# VCADual_Test.net
KiCad netlist of a schematic drawn in EAGLE
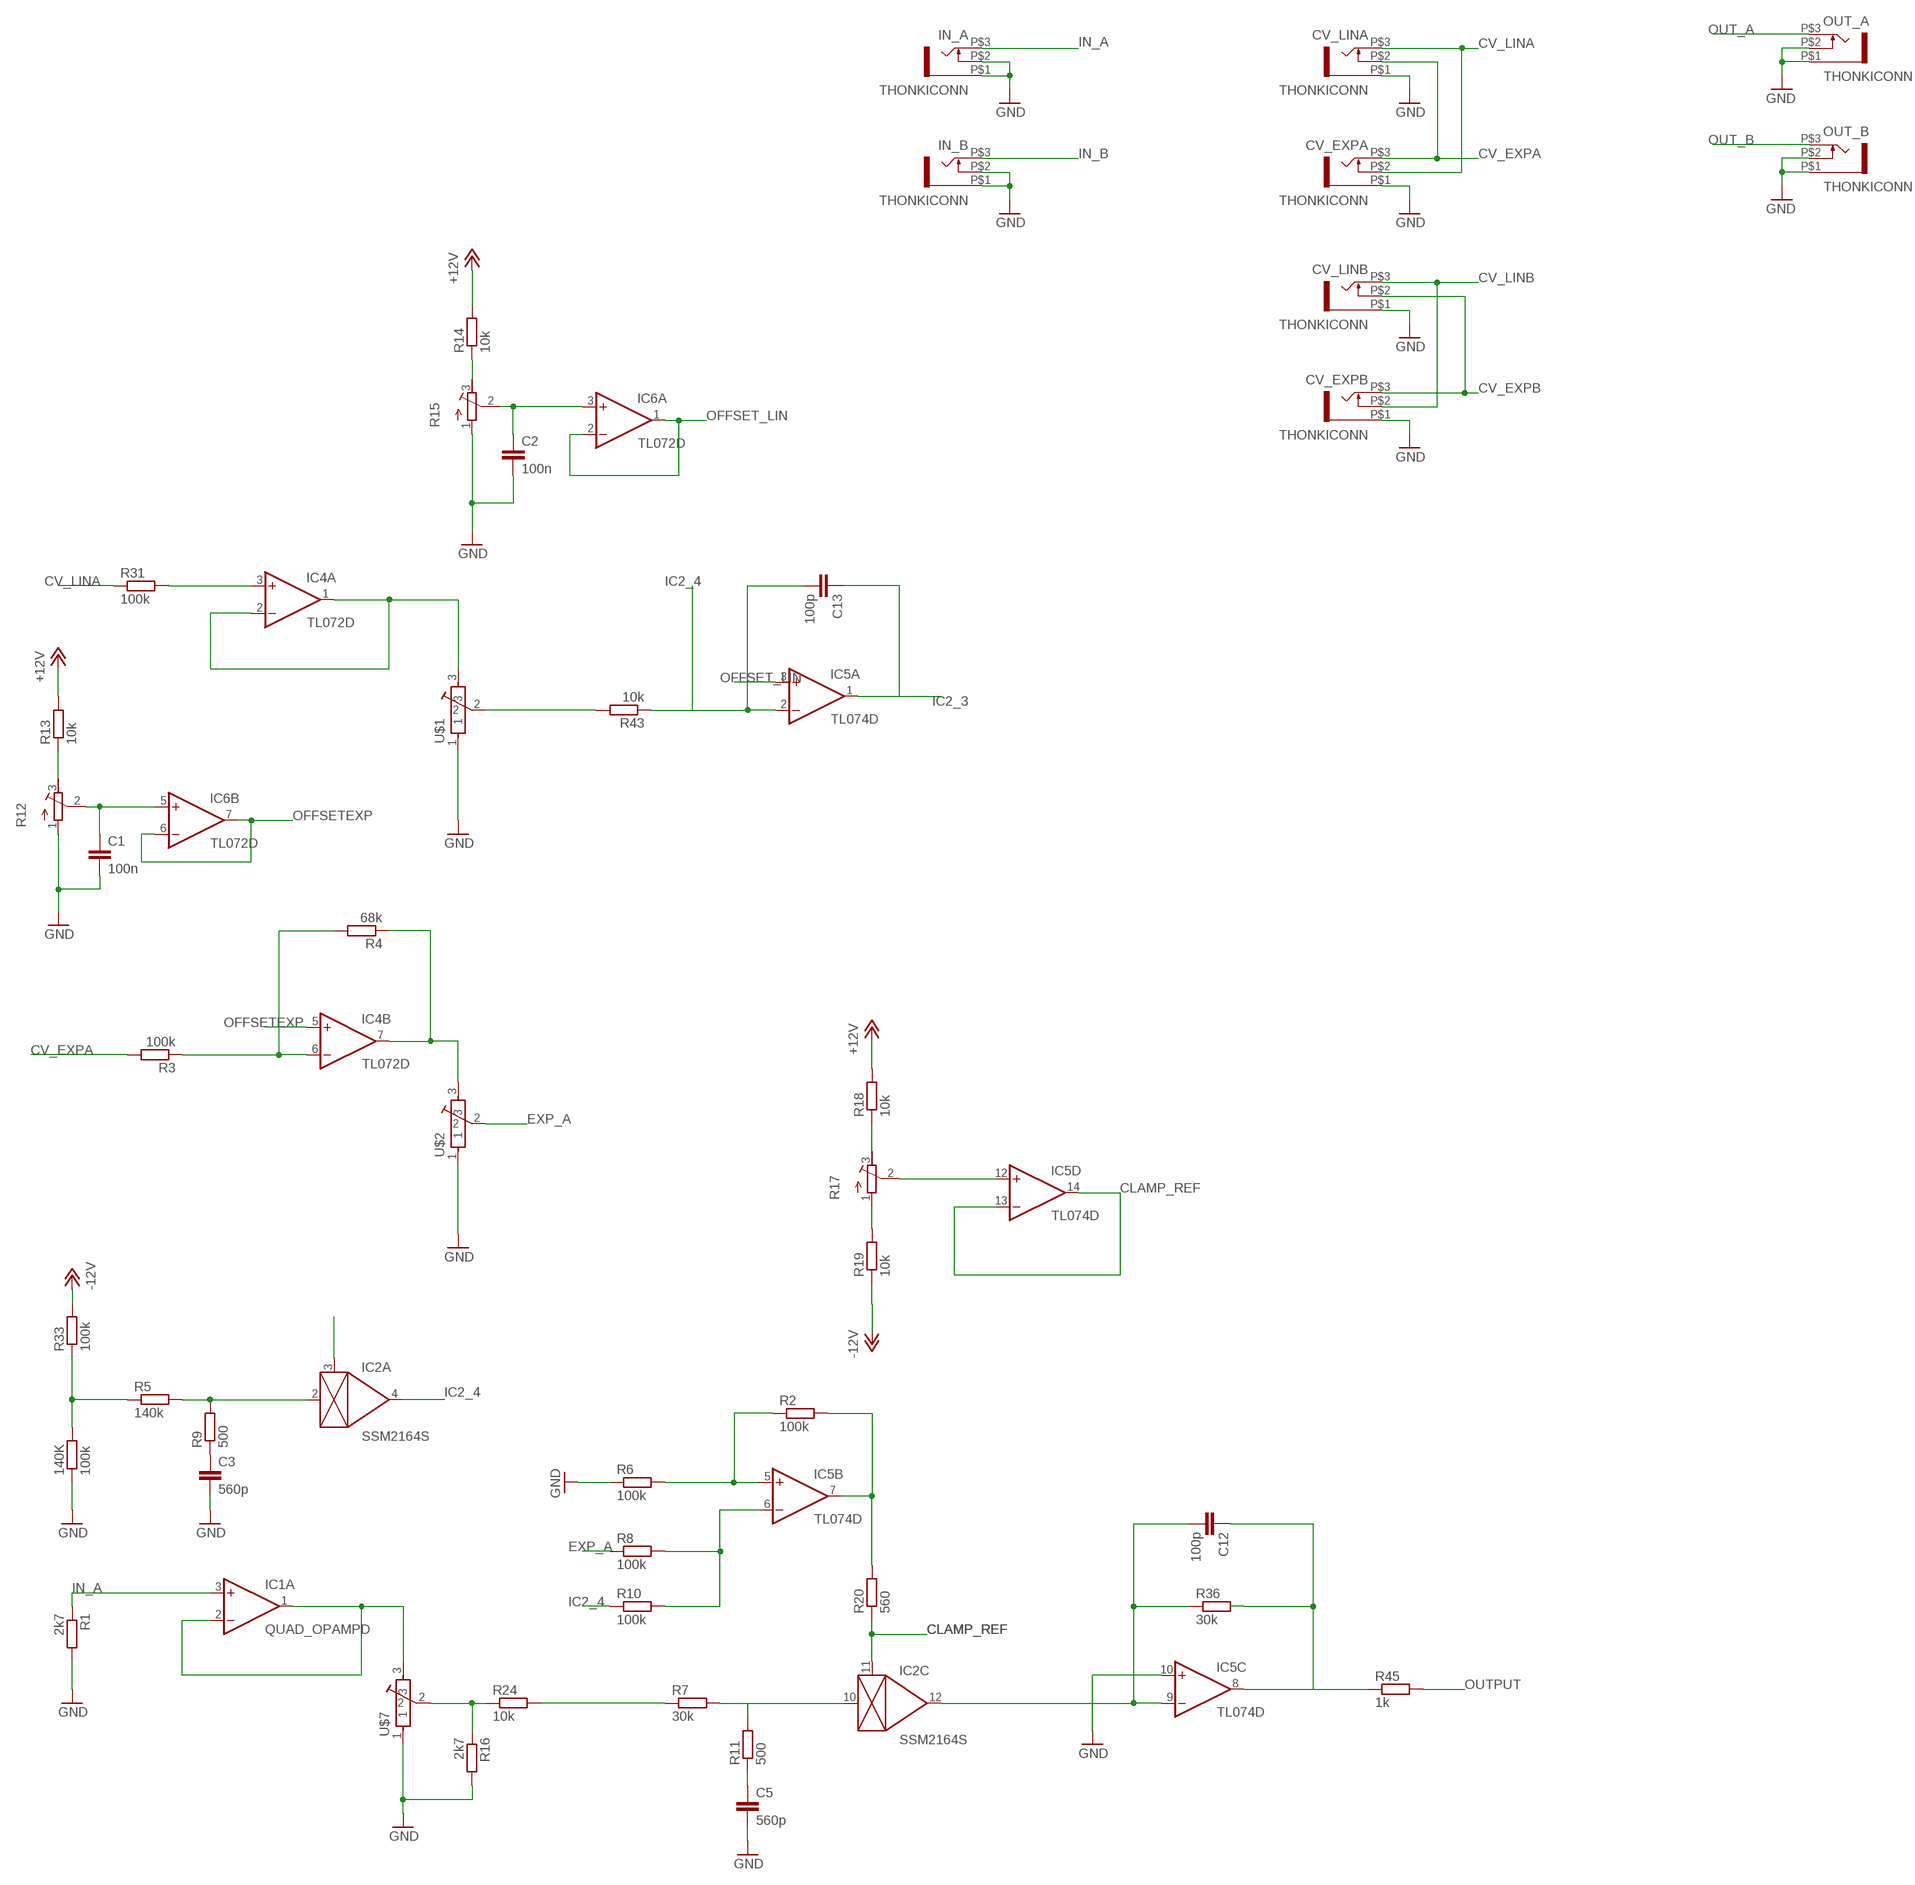
[diagram p0: schematic, sheet 1]

(export (version "E")
  (design (tool "Eeschema 10.0.6"))
  (components
    (comp (ref "140K")
      (value "100k")
      (footprint "eagle-import:0603")
      (libsource (lib "eagle-import") (part "R-EU_0603"))
    )
    (comp (ref "C1")
      (value "100n")
      (footprint "eagle-import:C0603K")
      (libsource (lib "eagle-import") (part "C-EUC0603K"))
    )
    (comp (ref "C2")
      (value "100n")
      (footprint "eagle-import:C0603K")
      (libsource (lib "eagle-import") (part "C-EUC0603K"))
    )
    (comp (ref "C3")
      (value "560p")
      (footprint "eagle-import:C0603K")
      (libsource (lib "eagle-import") (part "C-EUC0603K"))
    )
    (comp (ref "C5")
      (value "560p")
      (footprint "eagle-import:C0603K")
      (libsource (lib "eagle-import") (part "C-EUC0603K"))
    )
    (comp (ref "C12")
      (value "100p")
      (footprint "eagle-import:C0603K")
      (libsource (lib "eagle-import") (part "C-EUC0603K"))
    )
    (comp (ref "C13")
      (value "100p")
      (footprint "eagle-import:C0603K")
      (libsource (lib "eagle-import") (part "C-EUC0603K"))
    )
    (comp (ref "CV_EXPA")
      (value "THONKICONN")
      (footprint "eagle-import:THONKICONN")
      (libsource (lib "eagle-import") (part "THONKICONN"))
    )
    (comp (ref "CV_EXPB")
      (value "THONKICONN")
      (footprint "eagle-import:THONKICONN")
      (libsource (lib "eagle-import") (part "THONKICONN"))
    )
    (comp (ref "CV_LINA")
      (value "THONKICONN")
      (footprint "eagle-import:THONKICONN")
      (libsource (lib "eagle-import") (part "THONKICONN"))
    )
    (comp (ref "CV_LINB")
      (value "THONKICONN")
      (footprint "eagle-import:THONKICONN")
      (libsource (lib "eagle-import") (part "THONKICONN"))
    )
    (comp (ref "IC1")
      (value "QUAD_OPAMPD")
      (footprint "eagle-import:SO14")
      (libsource (lib "eagle-import") (part "QUAD_OPAMPD"))
    )
    (comp (ref "IC2")
      (value "SSM2164S")
      (footprint "eagle-import:SOIC16N")
      (libsource (lib "eagle-import") (part "SSM2164S"))
    )
    (comp (ref "IC4")
      (value "TL072D")
      (footprint "eagle-import:SO08")
      (libsource (lib "eagle-import") (part "TL072D"))
    )
    (comp (ref "IC5")
      (value "TL074D")
      (footprint "eagle-import:SO14")
      (libsource (lib "eagle-import") (part "TL074D"))
    )
    (comp (ref "IC6")
      (value "TL072D")
      (footprint "eagle-import:SO08")
      (libsource (lib "eagle-import") (part "TL072D"))
    )
    (comp (ref "IN_A")
      (value "THONKICONN")
      (footprint "eagle-import:THONKICONN")
      (libsource (lib "eagle-import") (part "THONKICONN"))
    )
    (comp (ref "IN_B")
      (value "THONKICONN")
      (footprint "eagle-import:THONKICONN")
      (libsource (lib "eagle-import") (part "THONKICONN"))
    )
    (comp (ref "OUT_A")
      (value "THONKICONN")
      (footprint "eagle-import:THONKICONN")
      (libsource (lib "eagle-import") (part "THONKICONN"))
    )
    (comp (ref "OUT_B")
      (value "THONKICONN")
      (footprint "eagle-import:THONKICONN")
      (libsource (lib "eagle-import") (part "THONKICONN"))
    )
    (comp (ref "R1")
      (value "2k7")
      (footprint "eagle-import:0603")
      (libsource (lib "eagle-import") (part "R-EU_0603"))
    )
    (comp (ref "R2")
      (value "100k")
      (footprint "eagle-import:0603")
      (libsource (lib "eagle-import") (part "R-EU_0603"))
    )
    (comp (ref "R3")
      (value "100k")
      (footprint "eagle-import:0603")
      (libsource (lib "eagle-import") (part "R-EU_0603"))
    )
    (comp (ref "R4")
      (value "68k")
      (footprint "eagle-import:0603")
      (libsource (lib "eagle-import") (part "R-EU_0603"))
    )
    (comp (ref "R5")
      (value "140k")
      (footprint "eagle-import:0603")
      (libsource (lib "eagle-import") (part "R-EU_0603"))
    )
    (comp (ref "R6")
      (value "100k")
      (footprint "eagle-import:0603")
      (libsource (lib "eagle-import") (part "R-EU_0603"))
    )
    (comp (ref "R7")
      (value "30k")
      (footprint "eagle-import:0603")
      (libsource (lib "eagle-import") (part "R-EU_0603"))
    )
    (comp (ref "R8")
      (value "100k")
      (footprint "eagle-import:0603")
      (libsource (lib "eagle-import") (part "R-EU_0603"))
    )
    (comp (ref "R9")
      (value "500")
      (footprint "eagle-import:0603")
      (libsource (lib "eagle-import") (part "R-EU_0603"))
    )
    (comp (ref "R10")
      (value "100k")
      (footprint "eagle-import:0603")
      (libsource (lib "eagle-import") (part "R-EU_0603"))
    )
    (comp (ref "R11")
      (value "500")
      (footprint "eagle-import:0603")
      (libsource (lib "eagle-import") (part "R-EU_0603"))
    )
    (comp (ref "R12")
      (value "R-TRIMM64X")
      (footprint "eagle-import:RTRIM64X")
      (libsource (lib "eagle-import") (part "R-TRIMM64X"))
    )
    (comp (ref "R13")
      (value "10k")
      (footprint "eagle-import:0603")
      (libsource (lib "eagle-import") (part "R-EU_0603"))
    )
    (comp (ref "R14")
      (value "10k")
      (footprint "eagle-import:0603")
      (libsource (lib "eagle-import") (part "R-EU_0603"))
    )
    (comp (ref "R15")
      (value "R-TRIMM64X")
      (footprint "eagle-import:RTRIM64X")
      (libsource (lib "eagle-import") (part "R-TRIMM64X"))
    )
    (comp (ref "R16")
      (value "2k7")
      (footprint "eagle-import:0603")
      (libsource (lib "eagle-import") (part "R-EU_0603"))
    )
    (comp (ref "R17")
      (value "R-TRIMM64X")
      (footprint "eagle-import:RTRIM64X")
      (libsource (lib "eagle-import") (part "R-TRIMM64X"))
    )
    (comp (ref "R18")
      (value "10k")
      (footprint "eagle-import:0603")
      (libsource (lib "eagle-import") (part "R-EU_0603"))
    )
    (comp (ref "R19")
      (value "10k")
      (footprint "eagle-import:0603")
      (libsource (lib "eagle-import") (part "R-EU_0603"))
    )
    (comp (ref "R20")
      (value "560")
      (footprint "eagle-import:0603")
      (libsource (lib "eagle-import") (part "R-EU_0603"))
    )
    (comp (ref "R24")
      (value "10k")
      (footprint "eagle-import:0603")
      (libsource (lib "eagle-import") (part "R-EU_0603"))
    )
    (comp (ref "R31")
      (value "100k")
      (footprint "eagle-import:0603")
      (libsource (lib "eagle-import") (part "R-EU_0603"))
    )
    (comp (ref "R33")
      (value "100k")
      (footprint "eagle-import:0603")
      (libsource (lib "eagle-import") (part "R-EU_0603"))
    )
    (comp (ref "R36")
      (value "30k")
      (footprint "eagle-import:0603")
      (libsource (lib "eagle-import") (part "R-EU_0603"))
    )
    (comp (ref "R43")
      (value "10k")
      (footprint "eagle-import:0603")
      (libsource (lib "eagle-import") (part "R-EU_0603"))
    )
    (comp (ref "R45")
      (value "1k")
      (footprint "eagle-import:0603")
      (libsource (lib "eagle-import") (part "R-EU_0603"))
    )
    (comp (ref "U$1")
      (value "POT-ALPS-RK09L1140")
      (footprint "eagle-import:POT-ALPS-RK09L1140")
      (libsource (lib "eagle-import") (part "POT-ALPS-RK09L1140"))
    )
    (comp (ref "U$2")
      (value "POT-ALPS-RK09L1140")
      (footprint "eagle-import:POT-ALPS-RK09L1140")
      (libsource (lib "eagle-import") (part "POT-ALPS-RK09L1140"))
    )
    (comp (ref "U$7")
      (value "POT-ALPS-RK09L1140")
      (footprint "eagle-import:POT-ALPS-RK09L1140")
      (libsource (lib "eagle-import") (part "POT-ALPS-RK09L1140"))
    )
  )
  (nets
    (net (code "1") (name "+12V") (class "Default")
      (node (ref "R13") (pin "2") (pinfunction "2_2") (pintype "passive"))
      (node (ref "R14") (pin "2") (pinfunction "2_2") (pintype "passive"))
      (node (ref "R18") (pin "2") (pinfunction "2_2") (pintype "passive"))
    )
    (net (code "2") (name "-12V") (class "Default")
      (node (ref "R19") (pin "1") (pinfunction "1_1") (pintype "passive"))
      (node (ref "R33") (pin "2") (pinfunction "2_2") (pintype "passive"))
    )
    (net (code "3") (name "/CLAMP_REF") (class "Default")
      (node (ref "IC2") (pin "11") (pinfunction "CTRL_11") (pintype "input"))
      (node (ref "IC5") (pin "13") (pinfunction "-IN_13") (pintype "input"))
      (node (ref "IC5") (pin "14") (pinfunction "OUT_14") (pintype "output"))
      (node (ref "R20") (pin "1") (pinfunction "1_1") (pintype "passive"))
    )
    (net (code "4") (name "/CV_EXPA") (class "Default")
      (node (ref "CV_EXPA") (pin "P$3") (pinfunction "3_P$3") (pintype "passive"))
      (node (ref "CV_LINA") (pin "P$2") (pinfunction "4_P$2") (pintype "passive"))
      (node (ref "R3") (pin "2") (pinfunction "2_2") (pintype "passive"))
    )
    (net (code "5") (name "/CV_EXPB") (class "Default")
      (node (ref "CV_EXPB") (pin "P$3") (pinfunction "3_P$3") (pintype "passive"))
      (node (ref "CV_LINB") (pin "P$2") (pinfunction "4_P$2") (pintype "passive"))
    )
    (net (code "6") (name "/CV_LINA") (class "Default")
      (node (ref "CV_EXPA") (pin "P$2") (pinfunction "4_P$2") (pintype "passive"))
      (node (ref "CV_LINA") (pin "P$3") (pinfunction "3_P$3") (pintype "passive"))
      (node (ref "R31") (pin "1") (pinfunction "1_1") (pintype "passive"))
    )
    (net (code "7") (name "/CV_LINB") (class "Default")
      (node (ref "CV_EXPB") (pin "P$2") (pinfunction "4_P$2") (pintype "passive"))
      (node (ref "CV_LINB") (pin "P$3") (pinfunction "3_P$3") (pintype "passive"))
    )
    (net (code "8") (name "/EXP_A") (class "Default")
      (node (ref "R8") (pin "1") (pinfunction "1_1") (pintype "passive"))
      (node (ref "U$2") (pin "2") (pinfunction "2_2") (pintype "bidirectional"))
    )
    (net (code "9") (name "/IC2_3") (class "Default")
      (node (ref "C13") (pin "1") (pinfunction "1_1") (pintype "passive"))
      (node (ref "IC2") (pin "3") (pinfunction "CTRL_3") (pintype "input"))
      (node (ref "IC5") (pin "1") (pinfunction "OUT_1") (pintype "output"))
    )
    (net (code "10") (name "/IC2_4") (class "Default")
      (node (ref "C13") (pin "2") (pinfunction "2_2") (pintype "passive"))
      (node (ref "IC2") (pin "4") (pinfunction "OUT_4") (pintype "output"))
      (node (ref "IC5") (pin "2") (pinfunction "-IN_2") (pintype "input"))
      (node (ref "R10") (pin "1") (pinfunction "1_1") (pintype "passive"))
      (node (ref "R43") (pin "1") (pinfunction "1_1") (pintype "passive"))
    )
    (net (code "11") (name "/IN_A") (class "Default")
      (node (ref "IC1") (pin "3") (pinfunction "+IN_3") (pintype "input"))
      (node (ref "IN_A") (pin "P$3") (pinfunction "3_P$3") (pintype "passive"))
      (node (ref "R1") (pin "1") (pinfunction "1_1") (pintype "passive"))
    )
    (net (code "12") (name "/IN_B") (class "Default")
      (node (ref "IN_B") (pin "P$3") (pinfunction "3_P$3") (pintype "passive"))
    )
    (net (code "13") (name "/OFFSETEXP") (class "Default")
      (node (ref "IC4") (pin "5") (pinfunction "+IN_5") (pintype "input"))
      (node (ref "IC6") (pin "6") (pinfunction "-IN_6") (pintype "input"))
      (node (ref "IC6") (pin "7") (pinfunction "OUT_7") (pintype "output"))
    )
    (net (code "14") (name "/OFFSET_LIN") (class "Default")
      (node (ref "IC5") (pin "3") (pinfunction "+IN_3") (pintype "input"))
      (node (ref "IC6") (pin "1") (pinfunction "OUT_1") (pintype "output"))
      (node (ref "IC6") (pin "2") (pinfunction "-IN_2") (pintype "input"))
    )
    (net (code "15") (name "/OUTPUT") (class "Default")
      (node (ref "R45") (pin "2") (pinfunction "2_2") (pintype "passive"))
    )
    (net (code "16") (name "/OUT_A") (class "Default")
      (node (ref "OUT_A") (pin "P$3") (pinfunction "3_P$3") (pintype "passive"))
    )
    (net (code "17") (name "/OUT_B") (class "Default")
      (node (ref "OUT_B") (pin "P$3") (pinfunction "3_P$3") (pintype "passive"))
    )
    (net (code "18") (name "GND") (class "Default")
      (node (ref "140K") (pin "1") (pinfunction "1_1") (pintype "passive"))
      (node (ref "C1") (pin "2") (pinfunction "2_2") (pintype "passive"))
      (node (ref "C2") (pin "2") (pinfunction "2_2") (pintype "passive"))
      (node (ref "C3") (pin "2") (pinfunction "2_2") (pintype "passive"))
      (node (ref "C5") (pin "2") (pinfunction "2_2") (pintype "passive"))
      (node (ref "CV_EXPA") (pin "P$1") (pinfunction "5_P$1") (pintype "passive"))
      (node (ref "CV_EXPB") (pin "P$1") (pinfunction "5_P$1") (pintype "passive"))
      (node (ref "CV_LINA") (pin "P$1") (pinfunction "5_P$1") (pintype "passive"))
      (node (ref "CV_LINB") (pin "P$1") (pinfunction "5_P$1") (pintype "passive"))
      (node (ref "IC5") (pin "10") (pinfunction "+IN_10") (pintype "input"))
      (node (ref "IN_A") (pin "P$1") (pinfunction "5_P$1") (pintype "passive"))
      (node (ref "IN_A") (pin "P$2") (pinfunction "4_P$2") (pintype "passive"))
      (node (ref "IN_B") (pin "P$1") (pinfunction "5_P$1") (pintype "passive"))
      (node (ref "IN_B") (pin "P$2") (pinfunction "4_P$2") (pintype "passive"))
      (node (ref "OUT_A") (pin "P$1") (pinfunction "5_P$1") (pintype "passive"))
      (node (ref "OUT_A") (pin "P$2") (pinfunction "4_P$2") (pintype "passive"))
      (node (ref "OUT_B") (pin "P$1") (pinfunction "5_P$1") (pintype "passive"))
      (node (ref "OUT_B") (pin "P$2") (pinfunction "4_P$2") (pintype "passive"))
      (node (ref "R1") (pin "2") (pinfunction "2_2") (pintype "passive"))
      (node (ref "R12") (pin "1") (pinfunction "A_1") (pintype "passive"))
      (node (ref "R15") (pin "1") (pinfunction "A_1") (pintype "passive"))
      (node (ref "R16") (pin "2") (pinfunction "2_2") (pintype "passive"))
      (node (ref "R6") (pin "1") (pinfunction "1_1") (pintype "passive"))
      (node (ref "U$1") (pin "1") (pinfunction "1_1") (pintype "bidirectional"))
      (node (ref "U$2") (pin "1") (pinfunction "1_1") (pintype "bidirectional"))
      (node (ref "U$7") (pin "1") (pinfunction "1_1") (pintype "bidirectional"))
    )
    (net (code "19") (name "Net-(140K-Pad2)") (class "Default")
      (node (ref "140K") (pin "2") (pinfunction "2_2") (pintype "passive"))
      (node (ref "R33") (pin "1") (pinfunction "1_1") (pintype "passive"))
      (node (ref "R5") (pin "1") (pinfunction "1_1") (pintype "passive"))
    )
    (net (code "20") (name "Net-(C3-Pad1)") (class "Default")
      (node (ref "C3") (pin "1") (pinfunction "1_1") (pintype "passive"))
      (node (ref "R9") (pin "1") (pinfunction "1_1") (pintype "passive"))
    )
    (net (code "21") (name "Net-(C5-Pad1)") (class "Default")
      (node (ref "C5") (pin "1") (pinfunction "1_1") (pintype "passive"))
      (node (ref "R11") (pin "1") (pinfunction "1_1") (pintype "passive"))
    )
    (net (code "22") (name "Net-(IC1A--IN)") (class "Default")
      (node (ref "IC1") (pin "1") (pinfunction "OUT_1") (pintype "output"))
      (node (ref "IC1") (pin "2") (pinfunction "-IN_2") (pintype "input"))
      (node (ref "U$7") (pin "3") (pinfunction "3_3") (pintype "bidirectional"))
    )
    (net (code "23") (name "Net-(IC2A-IN)") (class "Default")
      (node (ref "IC2") (pin "2") (pinfunction "IN_2") (pintype "input"))
      (node (ref "R5") (pin "2") (pinfunction "2_2") (pintype "passive"))
      (node (ref "R9") (pin "2") (pinfunction "2_2") (pintype "passive"))
    )
    (net (code "24") (name "Net-(IC2C-IN)") (class "Default")
      (node (ref "IC2") (pin "10") (pinfunction "IN_10") (pintype "input"))
      (node (ref "R11") (pin "2") (pinfunction "2_2") (pintype "passive"))
      (node (ref "R7") (pin "2") (pinfunction "2_2") (pintype "passive"))
    )
    (net (code "25") (name "Net-(IC2C-OUT)") (class "Default")
      (node (ref "C12") (pin "2") (pinfunction "2_2") (pintype "passive"))
      (node (ref "IC2") (pin "12") (pinfunction "OUT_12") (pintype "output"))
      (node (ref "IC5") (pin "9") (pinfunction "-IN_9") (pintype "input"))
      (node (ref "R36") (pin "1") (pinfunction "1_1") (pintype "passive"))
    )
    (net (code "26") (name "Net-(IC4A-+IN)") (class "Default")
      (node (ref "IC4") (pin "3") (pinfunction "+IN_3") (pintype "input"))
      (node (ref "R31") (pin "2") (pinfunction "2_2") (pintype "passive"))
    )
    (net (code "27") (name "Net-(IC4A--IN)") (class "Default")
      (node (ref "IC4") (pin "1") (pinfunction "OUT_1") (pintype "output"))
      (node (ref "IC4") (pin "2") (pinfunction "-IN_2") (pintype "input"))
      (node (ref "U$1") (pin "3") (pinfunction "3_3") (pintype "bidirectional"))
    )
    (net (code "28") (name "Net-(IC4B--IN)") (class "Default")
      (node (ref "IC4") (pin "6") (pinfunction "-IN_6") (pintype "input"))
      (node (ref "R3") (pin "1") (pinfunction "1_1") (pintype "passive"))
      (node (ref "R4") (pin "2") (pinfunction "2_2") (pintype "passive"))
    )
    (net (code "29") (name "Net-(IC4B-OUT)") (class "Default")
      (node (ref "IC4") (pin "7") (pinfunction "OUT_7") (pintype "output"))
      (node (ref "R4") (pin "1") (pinfunction "1_1") (pintype "passive"))
      (node (ref "U$2") (pin "3") (pinfunction "3_3") (pintype "bidirectional"))
    )
    (net (code "30") (name "Net-(IC5B-+IN)") (class "Default")
      (node (ref "IC5") (pin "5") (pinfunction "+IN_5") (pintype "input"))
      (node (ref "R2") (pin "1") (pinfunction "1_1") (pintype "passive"))
      (node (ref "R6") (pin "2") (pinfunction "2_2") (pintype "passive"))
    )
    (net (code "31") (name "Net-(IC5B-OUT)") (class "Default")
      (node (ref "IC5") (pin "7") (pinfunction "OUT_7") (pintype "output"))
      (node (ref "R2") (pin "2") (pinfunction "2_2") (pintype "passive"))
      (node (ref "R20") (pin "2") (pinfunction "2_2") (pintype "passive"))
    )
    (net (code "32") (name "Net-(IC5C-OUT)") (class "Default")
      (node (ref "C12") (pin "1") (pinfunction "1_1") (pintype "passive"))
      (node (ref "IC5") (pin "8") (pinfunction "OUT_8") (pintype "output"))
      (node (ref "R36") (pin "2") (pinfunction "2_2") (pintype "passive"))
      (node (ref "R45") (pin "1") (pinfunction "1_1") (pintype "passive"))
    )
    (net (code "33") (name "Net-(IC5D-+IN)") (class "Default")
      (node (ref "IC5") (pin "12") (pinfunction "+IN_12") (pintype "input"))
      (node (ref "R17") (pin "2") (pinfunction "S_2") (pintype "passive"))
    )
    (net (code "34") (name "Net-(IC6A-+IN)") (class "Default")
      (node (ref "C2") (pin "1") (pinfunction "1_1") (pintype "passive"))
      (node (ref "IC6") (pin "3") (pinfunction "+IN_3") (pintype "input"))
      (node (ref "R15") (pin "2") (pinfunction "S_2") (pintype "passive"))
    )
    (net (code "35") (name "Net-(IC6B-+IN)") (class "Default")
      (node (ref "C1") (pin "1") (pinfunction "1_1") (pintype "passive"))
      (node (ref "IC6") (pin "5") (pinfunction "+IN_5") (pintype "input"))
      (node (ref "R12") (pin "2") (pinfunction "S_2") (pintype "passive"))
    )
    (net (code "36") (name "Net-(R10-Pad2)") (class "Default")
      (node (ref "R10") (pin "2") (pinfunction "2_2") (pintype "passive"))
      (node (ref "R8") (pin "2") (pinfunction "2_2") (pintype "passive"))
    )
    (net (code "37") (name "Net-(R12-E)") (class "Default")
      (node (ref "R12") (pin "3") (pinfunction "E_3") (pintype "passive"))
      (node (ref "R13") (pin "1") (pinfunction "1_1") (pintype "passive"))
    )
    (net (code "38") (name "Net-(R15-E)") (class "Default")
      (node (ref "R14") (pin "1") (pinfunction "1_1") (pintype "passive"))
      (node (ref "R15") (pin "3") (pinfunction "E_3") (pintype "passive"))
    )
    (net (code "39") (name "Net-(R16-Pad1)") (class "Default")
      (node (ref "R16") (pin "1") (pinfunction "1_1") (pintype "passive"))
      (node (ref "R24") (pin "1") (pinfunction "1_1") (pintype "passive"))
      (node (ref "U$7") (pin "2") (pinfunction "2_2") (pintype "bidirectional"))
    )
    (net (code "40") (name "Net-(R17-A)") (class "Default")
      (node (ref "R17") (pin "1") (pinfunction "A_1") (pintype "passive"))
      (node (ref "R19") (pin "2") (pinfunction "2_2") (pintype "passive"))
    )
    (net (code "41") (name "Net-(R17-E)") (class "Default")
      (node (ref "R17") (pin "3") (pinfunction "E_3") (pintype "passive"))
      (node (ref "R18") (pin "1") (pinfunction "1_1") (pintype "passive"))
    )
    (net (code "42") (name "Net-(R24-Pad2)") (class "Default")
      (node (ref "R24") (pin "2") (pinfunction "2_2") (pintype "passive"))
      (node (ref "R7") (pin "1") (pinfunction "1_1") (pintype "passive"))
    )
    (net (code "43") (name "Net-(R43-Pad2)") (class "Default")
      (node (ref "R43") (pin "2") (pinfunction "2_2") (pintype "passive"))
      (node (ref "U$1") (pin "2") (pinfunction "2_2") (pintype "bidirectional"))
    )
    (net (code "44") (name "unconnected-(IC5B--IN-Pad6)") (class "Default")
      (node (ref "IC5") (pin "6") (pinfunction "-IN_6") (pintype "input"))
    )
  )
)
